# AST1013.net
KiCad netlist of a schematic drawn in EAGLE
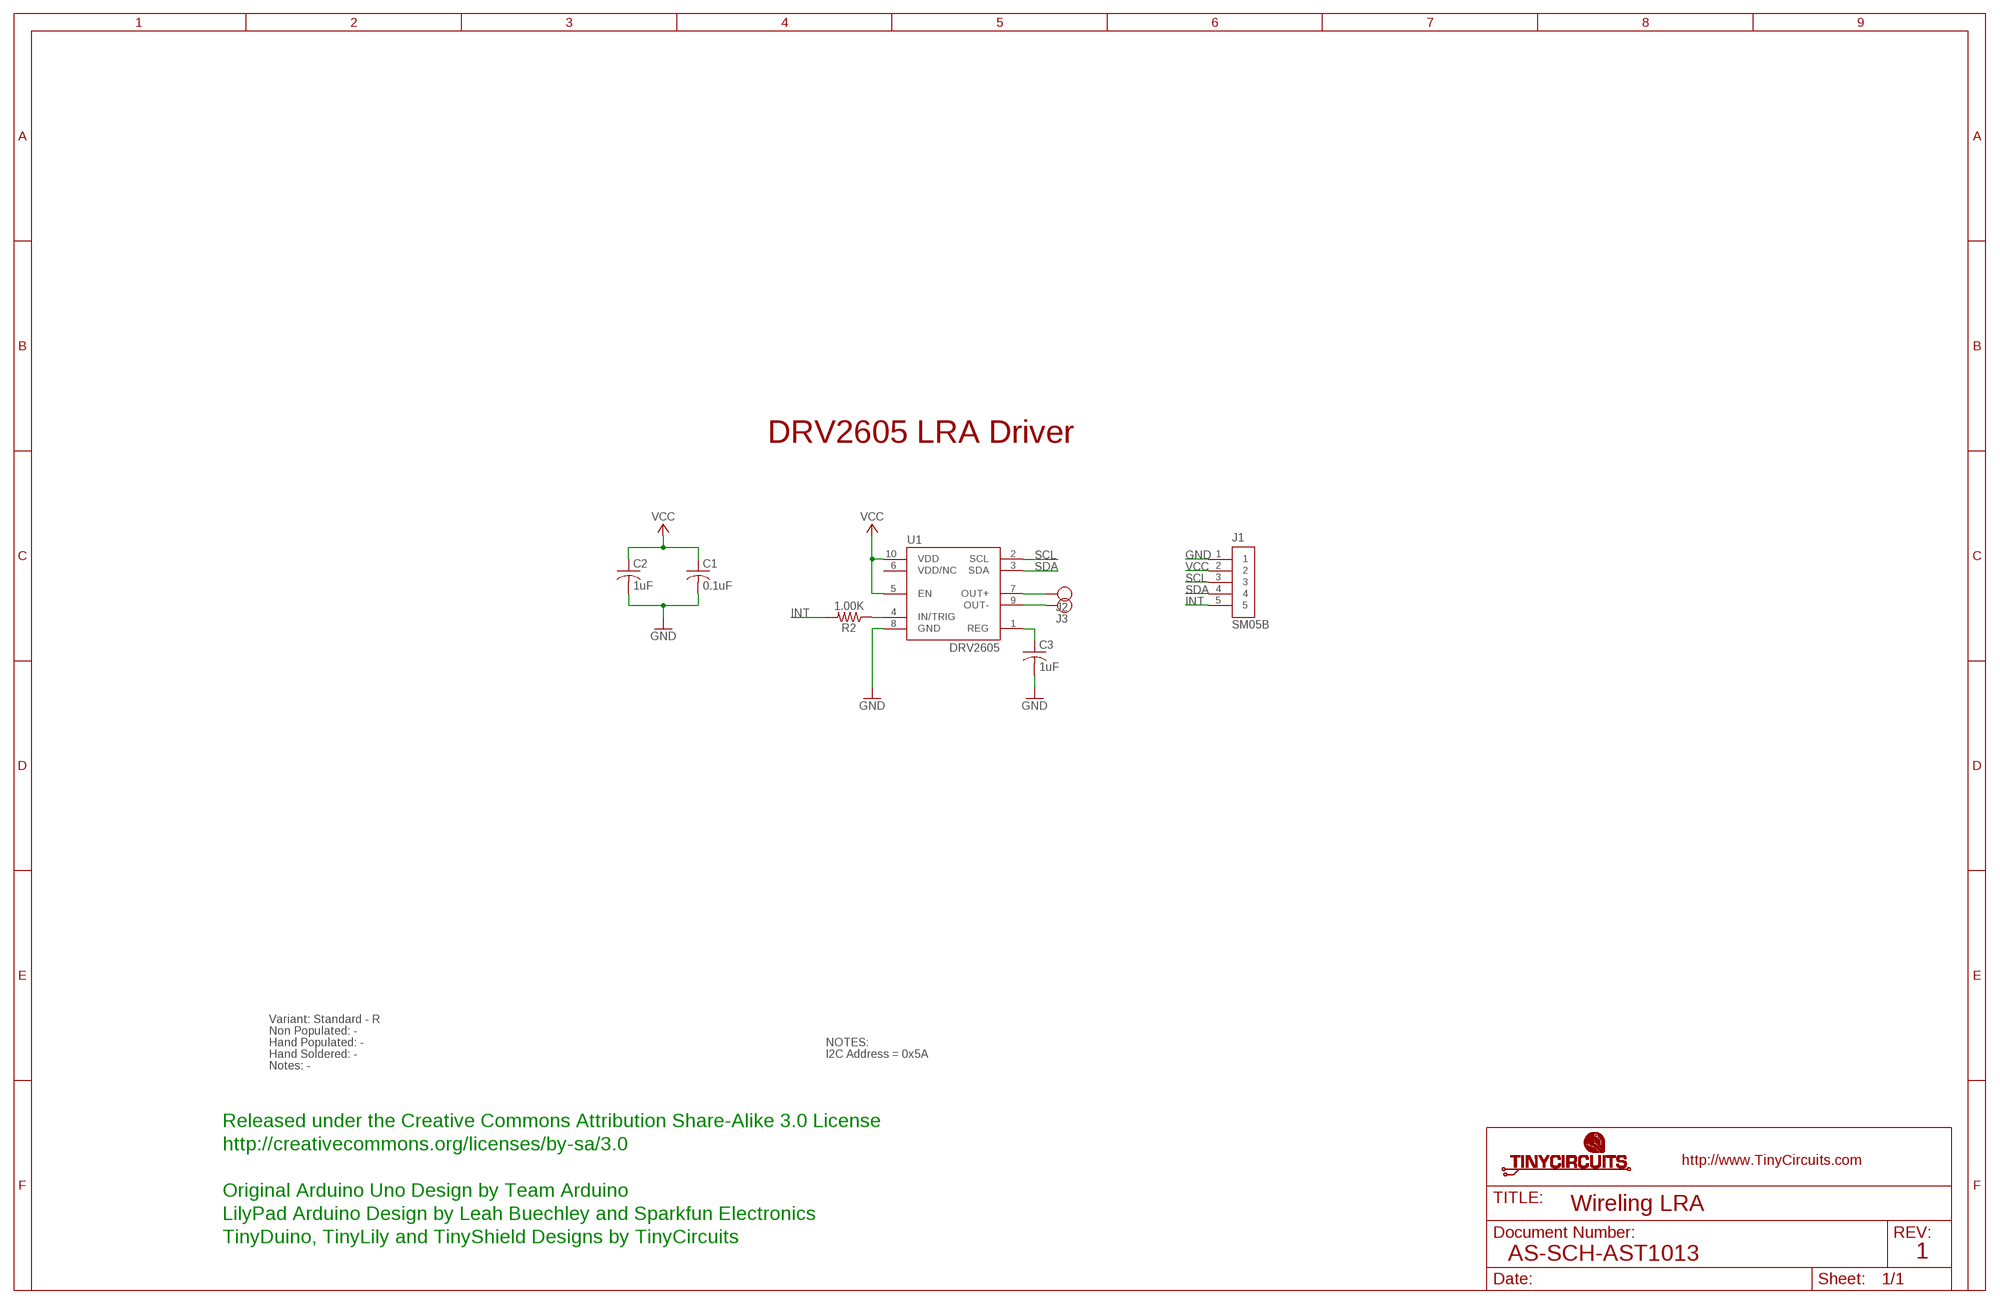
[diagram p0: schematic, sheet 1]

(export (version "E")
  (design (tool "Eeschema 10.0.6"))
  (components
    (comp (ref "C1")
      (value "0.1uF")
      (footprint "eagle-import:C0402")
      (fields (field (name "PARTNO") "AS-ITM-00008"))
      (libsource (lib "eagle-import") (part "AS-ITM-00008"))
    )
    (comp (ref "C2")
      (value "1uF")
      (footprint "eagle-import:C0603")
      (fields (field (name "PARTNO") "AS-ITM-00410") (field (name "PARTNO_1") "AS-ITM-00410"))
      (libsource (lib "eagle-import") (part "AS-ITM-00410"))
    )
    (comp (ref "C3")
      (value "1uF")
      (footprint "eagle-import:C0402")
      (fields (field (name "PARTNO") "AS-ITM-00105"))
      (libsource (lib "eagle-import") (part "AS-ITM-00105"))
    )
    (comp (ref "J1")
      (value "SM05B")
      (footprint "eagle-import:JST_SH_5X1")
      (fields (field (name "PARTNO") "AS-ITM-00340"))
      (libsource (lib "eagle-import") (part "AS-ITM-00340"))
    )
    (comp (ref "J2")
      (value "PIN_1X.1\"1")
      (footprint "eagle-import:1X.1__2")
      (libsource (lib "eagle-import") (part "PIN_1X.1{dblquote}1"))
    )
    (comp (ref "J3")
      (value "PIN_1X.1\"1")
      (footprint "eagle-import:1X.1__2")
      (libsource (lib "eagle-import") (part "PIN_1X.1{dblquote}1"))
    )
    (comp (ref "R2")
      (value "1.00K")
      (footprint "eagle-import:0402")
      (fields (field (name "PARTNO") "AS-ITM-00003") (field (name "PARTNO_1") "AS-ITM-00003"))
      (libsource (lib "eagle-import") (part "AS-ITM-00003"))
    )
    (comp (ref "U1")
      (value "DRV2605")
      (footprint "eagle-import:DGS(S-PDSO-G10)")
      (fields (field (name "PARTNO") "AS-ITM-00368"))
      (libsource (lib "eagle-import") (part "AS-ITM-00368"))
    )
  )
  (nets
    (net (code "1") (name "/INT") (class "Default")
      (node (ref "J1") (pin "5") (pinfunction "5_5") (pintype "bidirectional"))
      (node (ref "R2") (pin "2") (pinfunction "2_2") (pintype "passive"))
    )
    (net (code "2") (name "/SCL") (class "Default")
      (node (ref "J1") (pin "3") (pinfunction "3_3") (pintype "bidirectional"))
      (node (ref "U1") (pin "2") (pinfunction "SCL_2") (pintype "bidirectional"))
    )
    (net (code "3") (name "/SDA") (class "Default")
      (node (ref "J1") (pin "4") (pinfunction "4_4") (pintype "bidirectional"))
      (node (ref "U1") (pin "3") (pinfunction "SDA_3") (pintype "bidirectional"))
    )
    (net (code "4") (name "GND") (class "Default")
      (node (ref "C1") (pin "2") (pinfunction "2_2") (pintype "passive"))
      (node (ref "C2") (pin "2") (pinfunction "2_2") (pintype "passive"))
      (node (ref "C3") (pin "2") (pinfunction "2_2") (pintype "passive"))
      (node (ref "J1") (pin "1") (pinfunction "1_1") (pintype "bidirectional"))
      (node (ref "U1") (pin "8") (pinfunction "GND_8") (pintype "bidirectional"))
    )
    (net (code "5") (name "Net-(U1-IN{slash}TRIG)") (class "Default")
      (node (ref "R2") (pin "1") (pinfunction "1_1") (pintype "passive"))
      (node (ref "U1") (pin "4") (pinfunction "IN/TRIG_4") (pintype "bidirectional"))
    )
    (net (code "6") (name "Net-(U1-OUT+)") (class "Default")
      (node (ref "J2") (pin "1") (pinfunction "1_1") (pintype "bidirectional"))
      (node (ref "U1") (pin "7") (pinfunction "OUT+_7") (pintype "bidirectional"))
    )
    (net (code "7") (name "Net-(U1-OUT-)") (class "Default")
      (node (ref "J3") (pin "1") (pinfunction "1_1") (pintype "bidirectional"))
      (node (ref "U1") (pin "9") (pinfunction "OUT-_9") (pintype "bidirectional"))
    )
    (net (code "8") (name "Net-(U1-REG)") (class "Default")
      (node (ref "C3") (pin "1") (pinfunction "1_1") (pintype "passive"))
      (node (ref "U1") (pin "1") (pinfunction "REG_1") (pintype "bidirectional"))
    )
    (net (code "9") (name "VCC") (class "Default")
      (node (ref "C1") (pin "1") (pinfunction "1_1") (pintype "passive"))
      (node (ref "C2") (pin "1") (pinfunction "1_1") (pintype "passive"))
      (node (ref "J1") (pin "2") (pinfunction "2_2") (pintype "bidirectional"))
      (node (ref "U1") (pin "10") (pinfunction "VDD_10") (pintype "bidirectional"))
      (node (ref "U1") (pin "5") (pinfunction "EN_5") (pintype "bidirectional"))
    )
    (net (code "10") (name "unconnected-(U1-VDD{slash}NC-Pad6)") (class "Default")
      (node (ref "U1") (pin "6") (pinfunction "VDD/NC_6") (pintype "bidirectional"))
    )
  )
)
